# LM2587.net
KiCad netlist of a schematic drawn in Altium Designer
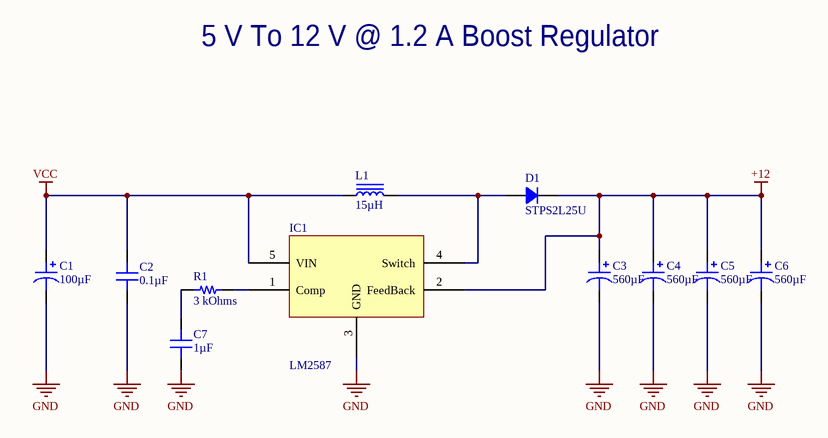
[diagram p0: LM2587.SchDoc]

(export (version "E")
  (design (tool "Eeschema 10.0.6"))
  (components
    (comp (ref "C1")
      (value "100µF")
      (footprint "CAP ALSMD 6.6MM H5.4MM")
      (description "CAP ALUM 100UF 20% 16V SMD")
      (fields
        (field (name "PART NUMBER") "AVS107M16D16T-F")
        (field (name "MANUFACTURER") "Cornell Dubilier Electronics (CDE)")
      )
      (libsource (lib "Celestial Altium Library - altium_library") (part "Polarised Capacitor"))
    )
    (comp (ref "C2")
      (value "0.1µF")
      (footprint "CAP 0805_2012")
      (description "CAP CER 0.1UF 25V Z5U 0805")
      (fields (field (name "PART NUMBER") "08053E104ZAT2A") (field (name "MANUFACTURER") "AVX Corporation"))
      (libsource (lib "Celestial Altium Library - altium_library") (part "Capacitor"))
    )
    (comp (ref "C3")
      (value "560µF")
      (footprint "CAP ALSMD 8.3MM H10.5MM")
      (description "CAP ALUM 560UF 20% 25V SMD")
      (fields (field (name "PART NUMBER") "UCV1E561MNL1GS") (field (name "MANUFACTURER") "Nichicon"))
      (libsource (lib "Celestial Altium Library - altium_library") (part "Polarised Capacitor"))
    )
    (comp (ref "C4")
      (value "560µF")
      (footprint "CAP ALSMD 8.3MM H10.5MM")
      (description "CAP ALUM 560UF 20% 25V SMD")
      (fields (field (name "PART NUMBER") "UCV1E561MNL1GS") (field (name "MANUFACTURER") "Nichicon"))
      (libsource (lib "Celestial Altium Library - altium_library") (part "Polarised Capacitor"))
    )
    (comp (ref "C5")
      (value "560µF")
      (footprint "CAP ALSMD 8.3MM H10.5MM")
      (description "CAP ALUM 560UF 20% 25V SMD")
      (fields (field (name "PART NUMBER") "UCV1E561MNL1GS") (field (name "MANUFACTURER") "Nichicon"))
      (libsource (lib "Celestial Altium Library - altium_library") (part "Polarised Capacitor"))
    )
    (comp (ref "C6")
      (value "560µF")
      (footprint "CAP ALSMD 8.3MM H10.5MM")
      (description "CAP ALUM 560UF 20% 25V SMD")
      (fields (field (name "PART NUMBER") "UCV1E561MNL1GS") (field (name "MANUFACTURER") "Nichicon"))
      (libsource (lib "Celestial Altium Library - altium_library") (part "Polarised Capacitor"))
    )
    (comp (ref "C7")
      (value "1µF")
      (footprint "CAP 0805_2012")
      (description "CAP CER 1UF 25V X7R 0805")
      (fields (field (name "PART NUMBER") "C0805C105K3RACTU") (field (name "MANUFACTURER") "KEMET"))
      (libsource (lib "Celestial Altium Library - altium_library") (part "Capacitor"))
    )
    (comp (ref "D1")
      (value "STPS2L25U")
      (footprint "DO214AA SMB")
      (description "DIODE SCHOTTKY 25V 2A SMB")
      (fields (field (name "MANUFACTURER") "STMicroelectronics"))
      (libsource (lib "Celestial Altium Library - altium_library") (part "Diode"))
    )
    (comp (ref "IC1")
      (value "LM2587")
      (footprint "AltiumLive:D2PAK - T0263")
      (libsource (lib "AltiumLive") (part "LM2587"))
    )
    (comp (ref "L1")
      (value "15µH")
      (footprint "AltiumLive:7447070")
      (description "FIXED IND 15UH 3.1A 27 MOHM SMD")
      (fields
        (field (name "PART NUMBER") "SLF10165T-150M3R13PF")
        (field (name "MANUFACTURER") "TDK Corporation")
      )
      (libsource (lib "Celestial Altium Library - altium_library") (part "Inductor"))
    )
    (comp (ref "R1")
      (value "3 kOhms")
      (footprint "RES 0805_2012")
      (description "RES 3K OHM 5% 1/4W 0805")
      (fields
        (field (name "PART NUMBER") "RPC0805JT3K00")
        (field (name "MANUFACTURER") "Stackpole Electronics Inc")
      )
      (libsource (lib "Celestial Altium Library - altium_library") (part "Resistor"))
    )
  )
  (nets
    (net (code "1") (name "+12") (class "Default")
      (node (ref "C3") (pin "1") (pinfunction "1_1") (pintype "passive"))
      (node (ref "C4") (pin "1") (pinfunction "1_1") (pintype "passive"))
      (node (ref "C5") (pin "1") (pinfunction "1_1") (pintype "passive"))
      (node (ref "C6") (pin "1") (pinfunction "1_1") (pintype "passive"))
      (node (ref "D1") (pin "2") (pinfunction "2_2") (pintype "passive"))
      (node (ref "IC1") (pin "2") (pinfunction "FeedBack_2") (pintype "passive"))
    )
    (net (code "2") (name "GND") (class "Default")
      (node (ref "C1") (pin "2") (pinfunction "2_2") (pintype "passive"))
      (node (ref "C2") (pin "1") (pinfunction "1_1") (pintype "passive"))
      (node (ref "C3") (pin "2") (pinfunction "2_2") (pintype "passive"))
      (node (ref "C4") (pin "2") (pinfunction "2_2") (pintype "passive"))
      (node (ref "C5") (pin "2") (pinfunction "2_2") (pintype "passive"))
      (node (ref "C6") (pin "2") (pinfunction "2_2") (pintype "passive"))
      (node (ref "C7") (pin "1") (pinfunction "1_1") (pintype "passive"))
      (node (ref "IC1") (pin "3") (pinfunction "GND_3") (pintype "passive"))
    )
    (net (code "3") (name "Net-(C7-Pad2)") (class "Default")
      (node (ref "C7") (pin "2") (pinfunction "2_2") (pintype "passive"))
      (node (ref "R1") (pin "1") (pinfunction "1_1") (pintype "passive"))
    )
    (net (code "4") (name "Net-(IC1-Comp)") (class "Default")
      (node (ref "IC1") (pin "1") (pinfunction "Comp_1") (pintype "passive"))
      (node (ref "R1") (pin "2") (pinfunction "2_2") (pintype "passive"))
    )
    (net (code "5") (name "Net-(IC1-Switch)") (class "Default")
      (node (ref "D1") (pin "1") (pinfunction "1_1") (pintype "passive"))
      (node (ref "IC1") (pin "4") (pinfunction "Switch_4") (pintype "passive"))
      (node (ref "L1") (pin "2") (pinfunction "2_2") (pintype "passive"))
    )
    (net (code "6") (name "VCC") (class "Default")
      (node (ref "C1") (pin "1") (pinfunction "1_1") (pintype "passive"))
      (node (ref "C2") (pin "2") (pinfunction "2_2") (pintype "passive"))
      (node (ref "IC1") (pin "5") (pinfunction "VIN_5") (pintype "passive"))
      (node (ref "L1") (pin "1") (pinfunction "1_1") (pintype "passive"))
    )
  )
)
